# MotorDriver.net
KiCad netlist of a schematic drawn in Altium Designer
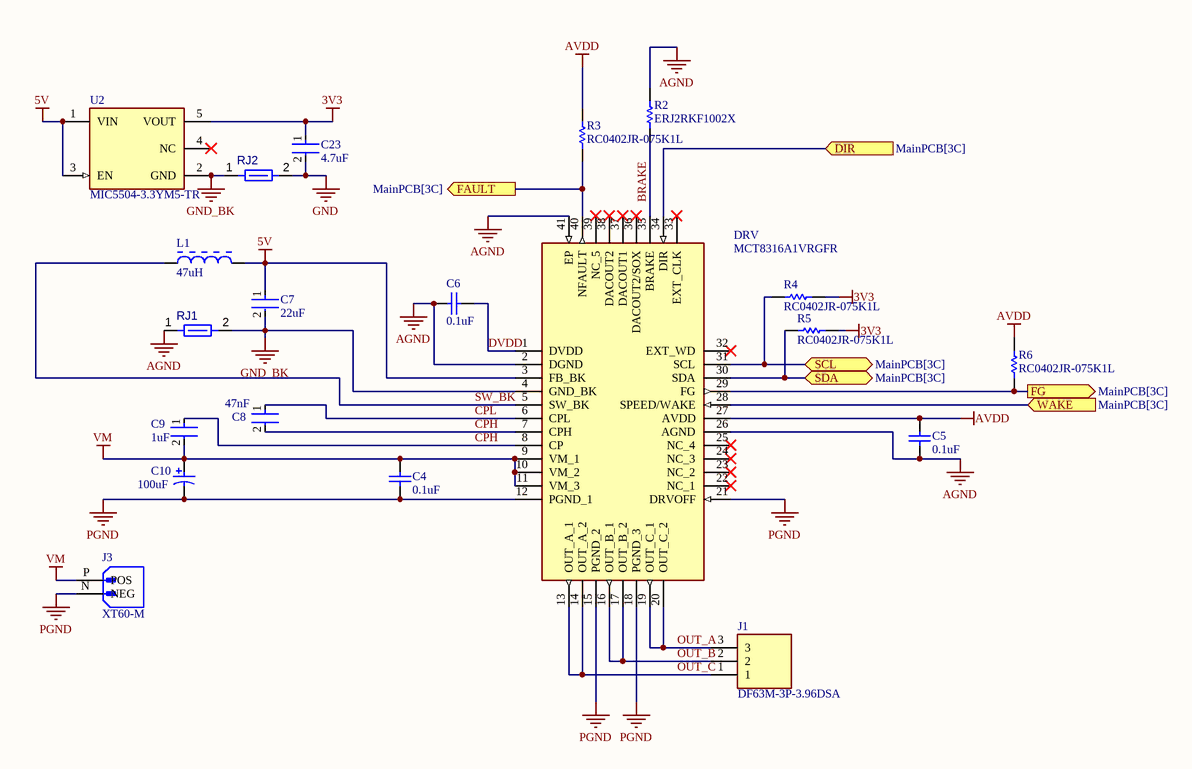
[diagram p0: MotorDriver.SchDoc]

(export (version "E")
  (design (tool "Eeschema 10.0.6"))
  (components
    (comp (ref "C4")
      (value "0.1uF")
      (footprint "CAPC1005X56X25LL10T15")
      (description "04023C104JAT2A")
      (fields (field (name "MANUFACTURER") "AVX Interconnect / Elco"))
      (libsource (lib "Altium Content Vault") (part "CAP"))
    )
    (comp (ref "C5")
      (value "0.1uF")
      (footprint "CAPC1005X56X25LL10T15")
      (description "04023C104JAT2A")
      (fields (field (name "MANUFACTURER") "AVX Interconnect / Elco"))
      (libsource (lib "Altium Content Vault") (part "CAP"))
    )
    (comp (ref "C6")
      (value "0.1uF")
      (footprint "CAPC1005X56X25LL10T15")
      (description "04023C104JAT2A")
      (fields (field (name "MANUFACTURER") "AVX Interconnect / Elco"))
      (libsource (lib "Altium Content Vault") (part "CAP"))
    )
    (comp (ref "C7")
      (value "22uF")
      (footprint "FP-1206-L_3_2_0_2-W_1_6_0-IPC_C")
      (description "12066D226MAT2A")
      (fields (field (name "TOLERANCE") "20%") (field (name "VOLTAGE") "6.3V"))
      (libsource (lib "Altium Content Vault") (part "02cd4be3c70576c341d710602a673aa"))
    )
    (comp (ref "C8")
      (value "47nF")
      (footprint "FP-CC0402-MFG")
      (description "CC0402KRX7R8BB473")
      (fields
        (field (name "MANUFACTURER") "YAGEO")
        (field (name "OCTOPART") "https://octopart.com/cc0402krx7r8bb473-yageo-22850998")
      )
      (libsource (lib "Altium Content Vault") (part "11868f565c42a9108669ba33697ecf6"))
    )
    (comp (ref "C9")
      (value "1uF")
      (footprint "FP-C1005-050-0_05-IPC_C")
      (description "C1005X5R1V105K050BC")
      (fields (field (name "TOLERANCE") "10%"))
      (libsource (lib "Altium Content Vault") (part "b4654b650e69147ec39a6b967a45e02"))
    )
    (comp (ref "C10")
      (value "100uF")
      (footprint "PNSC-FK-V-D8_V")
      (description "EEEFK1E101XP")
      (fields (field (name "MANUFACTURER") "Panasonic"))
      (libsource (lib "Altium Content Vault") (part "CAP-P-2"))
    )
    (comp (ref "C23")
      (value "4.7uF")
      (footprint "FP-C1005-050-0_15-MFG")
      (description "CAP CER 4.7UF 10V X5R 0402 C1005X5R1A475K050BC")
      (fields (field (name "TOLERANCE") "10%"))
      (libsource (lib "Altium Content Vault") (part "b4654b650e69147ec39a6b967a45e02"))
    )
    (comp (ref "DRV")
      (value "MCT8316A1VRGFR")
      (footprint "SamacSys:QFN50P500X700X100-41N-D")
      (description "Integrated Circuit")
      (fields (field (name "MOUSER PART NUMBER") "595-MCT8316A1VRGFR"))
      (libsource (lib "*") (part "MCT8316A1VRGFR"))
    )
    (comp (ref "J1")
      (value "DF63M-3P-3.96DSA")
      (footprint "SamacSys:DF63M3P396DSA")
      (description "Connector")
      (fields (field (name "MOUSER PART NUMBER") "798-DF63M-3P-3.96DSA"))
      (libsource (lib "*") (part "DF63M-3P-3.96DSA"))
    )
    (comp (ref "J3")
      (value "XT60-M")
      (footprint "AMASS_XT60-M")
      (description "Plug; DC supply; XT60; male; PIN: 2; for cable; soldered; 30A; 500V")
      (fields (field (name "MF") "AMASS"))
      (libsource (lib "XT60-M") (part "XT60-M"))
    )
    (comp (ref "L1")
      (value "47uH")
      (footprint "BOUR-SRN3015-2_V")
      (description "SRN3015-470M")
      (fields (field (name "MANUFACTURER") "Bourns"))
      (libsource (lib "Altium Content Vault") (part "BOUR-IND-2A"))
    )
    (comp (ref "R2")
      (value "ERJ2RKF1002X")
      (footprint "RESC1005X40X25LL05T05")
      (description "Chip Resistor, 10 KOhm, +/- 1%, 0.1 W, -55 to 155 degC, 0402 (1005 Metric), RoHS, Tape and Reel")
      (fields (field (name "TOLERANCE") "1%") (field (name "MANUFACTURER") "Panasonic"))
      (libsource (lib "Altium Content Vault") (part "RES-2"))
    )
    (comp (ref "R3")
      (value "RC0402JR-075K1L")
      (footprint "RESC1005X40X25ML05T10")
      (fields (field (name "MANUFACTURER") "Yageo / Phycomp"))
      (libsource (lib "Altium Content Vault") (part "RES"))
    )
    (comp (ref "R4")
      (value "RC0402JR-075K1L")
      (footprint "RESC1005X40X25ML05T10")
      (fields (field (name "MANUFACTURER") "Yageo / Phycomp"))
      (libsource (lib "Altium Content Vault") (part "RES"))
    )
    (comp (ref "R5")
      (value "RC0402JR-075K1L")
      (footprint "RESC1005X40X25ML05T10")
      (fields (field (name "MANUFACTURER") "Yageo / Phycomp"))
      (libsource (lib "Altium Content Vault") (part "RES"))
    )
    (comp (ref "R6")
      (value "RC0402JR-075K1L")
      (footprint "RESC1005X40X25ML05T10")
      (fields (field (name "MANUFACTURER") "Yageo / Phycomp"))
      (libsource (lib "Altium Content Vault") (part "RES"))
    )
    (comp (ref "RJ1")
      (value "Net Tie 10x8mil")
      (footprint "New footprint 1")
      (libsource (lib "Default") (part "CMP-00022-00002-2"))
    )
    (comp (ref "RJ2")
      (value "Net Tie 10x8mil")
      (footprint "New footprint 1")
      (libsource (lib "Default") (part "CMP-00022-00002-2"))
    )
    (comp (ref "U2")
      (value "MIC5504-3.3YM5-TR")
      (footprint "FP-SOT23-5LD-PL-1-MFG")
      (description "IC REG LINEAR 3.3V 300MA SOT23-5")
      (libsource (lib "Altium Content Vault") (part "96048095611b4a9579e1e315950d302"))
    )
  )
  (nets
    (net (code "1") (name "/BRAKE") (class "Default")
      (node (ref "DRV") (pin "35") (pinfunction "BRAKE_35") (pintype "passive"))
      (node (ref "R2") (pin "1") (pinfunction "1_1") (pintype "passive"))
    )
    (net (code "2") (name "/CPH") (class "Default")
      (node (ref "C8") (pin "2") (pinfunction "2_2") (pintype "passive"))
      (node (ref "C9") (pin "1") (pinfunction "1_1") (pintype "passive"))
      (node (ref "DRV") (pin "7") (pinfunction "CPH_7") (pintype "passive"))
      (node (ref "DRV") (pin "8") (pinfunction "CP_8") (pintype "passive"))
    )
    (net (code "3") (name "/CPL") (class "Default")
      (node (ref "C8") (pin "1") (pinfunction "1_1") (pintype "passive"))
      (node (ref "DRV") (pin "6") (pinfunction "CPL_6") (pintype "passive"))
    )
    (net (code "4") (name "/DIR") (class "Default")
      (node (ref "DRV") (pin "34") (pinfunction "DIR_34") (pintype "input"))
    )
    (net (code "5") (name "/DVDD") (class "Default")
      (node (ref "C6") (pin "2") (pinfunction "2_2") (pintype "passive"))
      (node (ref "DRV") (pin "1") (pinfunction "DVDD_1") (pintype "power_in"))
    )
    (net (code "6") (name "/FAULT") (class "Default")
      (node (ref "DRV") (pin "40") (pinfunction "NFAULT_40") (pintype "output"))
      (node (ref "R3") (pin "2") (pinfunction "2_2") (pintype "passive"))
    )
    (net (code "7") (name "/FG") (class "Default")
      (node (ref "DRV") (pin "29") (pinfunction "FG_29") (pintype "output"))
      (node (ref "R6") (pin "1") (pinfunction "1_1") (pintype "passive"))
    )
    (net (code "8") (name "/OUT_A") (class "Default")
      (node (ref "DRV") (pin "19") (pinfunction "OUT_C_1_19") (pintype "output"))
      (node (ref "DRV") (pin "20") (pinfunction "OUT_C_2_20") (pintype "passive"))
      (node (ref "J1") (pin "3") (pinfunction "3_3") (pintype "passive"))
    )
    (net (code "9") (name "/OUT_B") (class "Default")
      (node (ref "DRV") (pin "16") (pinfunction "OUT_B_1_16") (pintype "output"))
      (node (ref "DRV") (pin "17") (pinfunction "OUT_B_2_17") (pintype "passive"))
      (node (ref "J1") (pin "2") (pinfunction "2_2") (pintype "passive"))
    )
    (net (code "10") (name "/OUT_C") (class "Default")
      (node (ref "DRV") (pin "13") (pinfunction "OUT_A_1_13") (pintype "output"))
      (node (ref "DRV") (pin "14") (pinfunction "OUT_A_2_14") (pintype "passive"))
      (node (ref "J1") (pin "1") (pinfunction "1_1") (pintype "passive"))
    )
    (net (code "11") (name "/SCL") (class "Default")
      (node (ref "DRV") (pin "31") (pinfunction "SCL_31") (pintype "open_collector"))
      (node (ref "R4") (pin "1") (pinfunction "1_1") (pintype "passive"))
    )
    (net (code "12") (name "/SDA") (class "Default")
      (node (ref "DRV") (pin "30") (pinfunction "SDA_30") (pintype "open_collector"))
      (node (ref "R5") (pin "1") (pinfunction "1_1") (pintype "passive"))
    )
    (net (code "13") (name "/SW_BK") (class "Default")
      (node (ref "DRV") (pin "5") (pinfunction "SW_BK_5") (pintype "passive"))
      (node (ref "L1") (pin "1") (pinfunction "1_1") (pintype "passive"))
    )
    (net (code "14") (name "/WAKE") (class "Default")
      (node (ref "DRV") (pin "28") (pinfunction "SPEED/WAKE_28") (pintype "input"))
    )
    (net (code "15") (name "3V3") (class "Default")
      (node (ref "C23") (pin "1") (pinfunction "1_1") (pintype "passive"))
      (node (ref "R4") (pin "2") (pinfunction "2_2") (pintype "passive"))
      (node (ref "R5") (pin "2") (pinfunction "2_2") (pintype "passive"))
      (node (ref "U2") (pin "5") (pinfunction "VOUT_5") (pintype "power_in"))
    )
    (net (code "16") (name "5V") (class "Default")
      (node (ref "C7") (pin "1") (pinfunction "1_1") (pintype "passive"))
      (node (ref "DRV") (pin "3") (pinfunction "FB_BK_3") (pintype "power_in"))
      (node (ref "L1") (pin "2") (pinfunction "2_2") (pintype "passive"))
      (node (ref "U2") (pin "1") (pinfunction "VIN_1") (pintype "power_in"))
      (node (ref "U2") (pin "3") (pinfunction "EN_3") (pintype "input"))
    )
    (net (code "17") (name "AGND") (class "Default")
      (node (ref "C5") (pin "1") (pinfunction "1_1") (pintype "passive"))
      (node (ref "C6") (pin "1") (pinfunction "1_1") (pintype "passive"))
      (node (ref "DRV") (pin "2") (pinfunction "DGND_2") (pintype "power_in"))
      (node (ref "DRV") (pin "26") (pinfunction "AGND_26") (pintype "power_in"))
      (node (ref "DRV") (pin "41") (pinfunction "EP_41") (pintype "input"))
      (node (ref "R2") (pin "2") (pinfunction "2_2") (pintype "passive"))
      (node (ref "RJ1") (pin "1") (pinfunction "1_1") (pintype "passive"))
    )
    (net (code "18") (name "AVDD") (class "Default")
      (node (ref "C5") (pin "2") (pinfunction "2_2") (pintype "passive"))
      (node (ref "DRV") (pin "27") (pinfunction "AVDD_27") (pintype "power_in"))
      (node (ref "R3") (pin "1") (pinfunction "1_1") (pintype "passive"))
      (node (ref "R6") (pin "2") (pinfunction "2_2") (pintype "passive"))
    )
    (net (code "19") (name "GND") (class "Default")
      (node (ref "C23") (pin "2") (pinfunction "2_2") (pintype "passive"))
      (node (ref "RJ2") (pin "2") (pinfunction "2_2") (pintype "passive"))
    )
    (net (code "20") (name "GND_BK") (class "Default")
      (node (ref "C7") (pin "2") (pinfunction "2_2") (pintype "passive"))
      (node (ref "DRV") (pin "4") (pinfunction "GND_BK_4") (pintype "power_in"))
      (node (ref "RJ1") (pin "2") (pinfunction "2_2") (pintype "passive"))
      (node (ref "RJ2") (pin "1") (pinfunction "1_1") (pintype "passive"))
      (node (ref "U2") (pin "2") (pinfunction "GND_2") (pintype "power_in"))
    )
    (net (code "21") (name "PGND") (class "Default")
      (node (ref "C10") (pin "2") (pinfunction "2_2") (pintype "passive"))
      (node (ref "C4") (pin "1") (pinfunction "1_1") (pintype "passive"))
      (node (ref "DRV") (pin "12") (pinfunction "PGND_1_12") (pintype "power_in"))
      (node (ref "DRV") (pin "15") (pinfunction "PGND_2_15") (pintype "power_in"))
      (node (ref "DRV") (pin "18") (pinfunction "PGND_3_18") (pintype "power_in"))
      (node (ref "DRV") (pin "21") (pinfunction "DRVOFF_21") (pintype "input"))
      (node (ref "J3") (pin "N") (pinfunction "NEG_N") (pintype "passive"))
    )
    (net (code "22") (name "VM") (class "Default")
      (node (ref "C10") (pin "1") (pinfunction "1_1") (pintype "passive"))
      (node (ref "C4") (pin "2") (pinfunction "2_2") (pintype "passive"))
      (node (ref "C9") (pin "2") (pinfunction "2_2") (pintype "passive"))
      (node (ref "DRV") (pin "10") (pinfunction "VM_2_10") (pintype "power_in"))
      (node (ref "DRV") (pin "11") (pinfunction "VM_3_11") (pintype "power_in"))
      (node (ref "DRV") (pin "9") (pinfunction "VM_1_9") (pintype "power_in"))
      (node (ref "J3") (pin "P") (pinfunction "POS_P") (pintype "passive"))
    )
    (net (code "23") (name "unconnected-(DRV-DACOUT1-Pad37)") (class "Default")
      (node (ref "DRV") (pin "37") (pinfunction "DACOUT1_37") (pintype "passive+no_connect"))
    )
    (net (code "24") (name "unconnected-(DRV-DACOUT2-Pad38)") (class "Default")
      (node (ref "DRV") (pin "38") (pinfunction "DACOUT2_38") (pintype "passive+no_connect"))
    )
    (net (code "25") (name "unconnected-(DRV-DACOUT2{slash}SOX-Pad36)") (class "Default")
      (node (ref "DRV") (pin "36") (pinfunction "DACOUT2/SOX_36") (pintype "passive+no_connect"))
    )
    (net (code "26") (name "unconnected-(DRV-EXT_CLK-Pad33)") (class "Default")
      (node (ref "DRV") (pin "33") (pinfunction "EXT_CLK_33") (pintype "passive+no_connect"))
    )
    (net (code "27") (name "unconnected-(DRV-EXT_WD-Pad32)") (class "Default")
      (node (ref "DRV") (pin "32") (pinfunction "EXT_WD_32") (pintype "passive+no_connect"))
    )
    (net (code "28") (name "unconnected-(DRV-NC_1-Pad22)") (class "Default")
      (node (ref "DRV") (pin "22") (pinfunction "NC_1_22") (pintype "passive+no_connect"))
    )
    (net (code "29") (name "unconnected-(DRV-NC_2-Pad23)") (class "Default")
      (node (ref "DRV") (pin "23") (pinfunction "NC_2_23") (pintype "passive+no_connect"))
    )
    (net (code "30") (name "unconnected-(DRV-NC_3-Pad24)") (class "Default")
      (node (ref "DRV") (pin "24") (pinfunction "NC_3_24") (pintype "passive+no_connect"))
    )
    (net (code "31") (name "unconnected-(DRV-NC_4-Pad25)") (class "Default")
      (node (ref "DRV") (pin "25") (pinfunction "NC_4_25") (pintype "passive+no_connect"))
    )
    (net (code "32") (name "unconnected-(DRV-NC_5-Pad39)") (class "Default")
      (node (ref "DRV") (pin "39") (pinfunction "NC_5_39") (pintype "passive+no_connect"))
    )
    (net (code "33") (name "unconnected-(U2-NC-Pad4)") (class "Default")
      (node (ref "U2") (pin "4") (pinfunction "NC_4") (pintype "passive+no_connect"))
    )
  )
)
